# SCH_HackerCard.net
KiCad netlist of a schematic drawn in EasyEDA
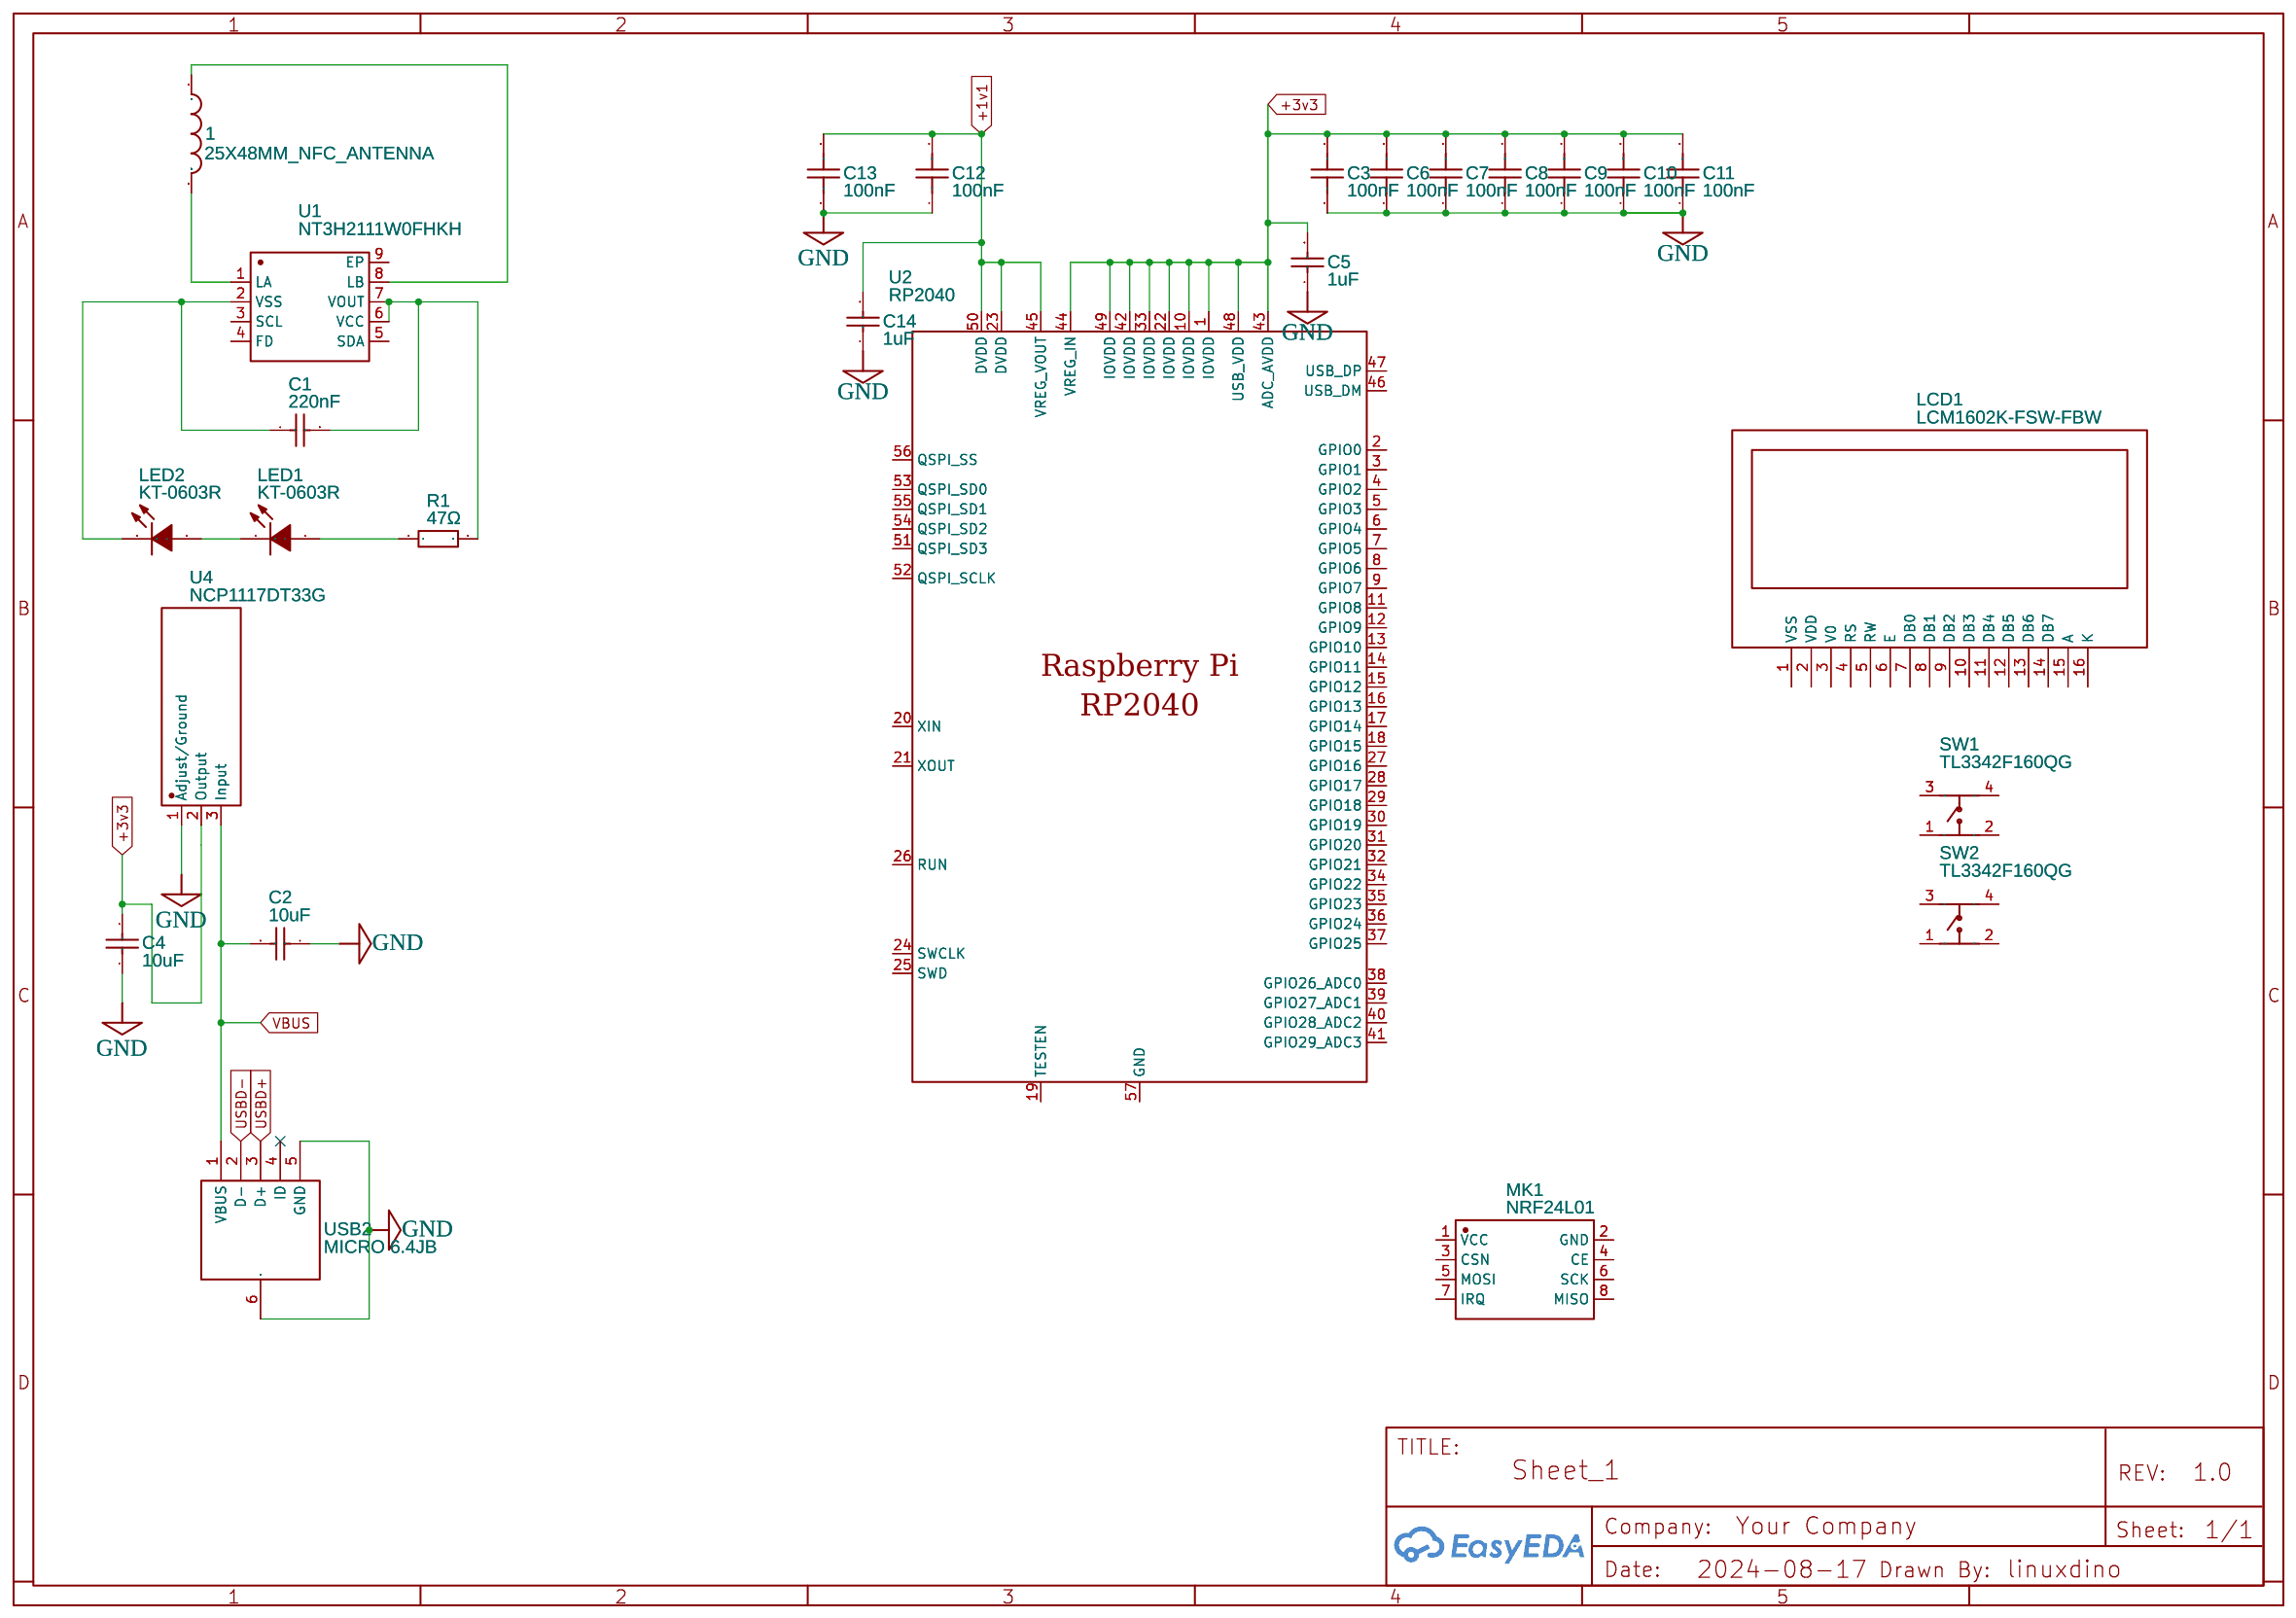
[diagram p0: schematic sheet]

(export (version "E")
  (design (tool "Eeschema 10.0.6"))
  (components
    (comp (ref "1") (value "25X48MM_NFC_ANTENNA") (libsource (lib "") (part "25X48MM_NFC_ANTENNA")))
    (comp (ref "C1")
      (value "220nF")
      (fields
        (field (name "Manufacturer Part") "CL10B224KA8NNNC")
        (field (name "Manufacturer") "SAMSUNG(三星)")
      )
      (libsource (lib "") (part "CL10B224KA8NNNC"))
    )
    (comp (ref "C2")
      (value "10uF")
      (fields
        (field (name "Manufacturer Part") "CL31A106KOHNNNE")
        (field (name "Manufacturer") "SAMSUNG(三星)")
      )
      (libsource (lib "") (part "CL31A106KOHNNNE"))
    )
    (comp (ref "C3")
      (value "100nF")
      (fields
        (field (name "Manufacturer Part") "CL10B104KB8NNNC")
        (field (name "Manufacturer") "SAMSUNG(三星)")
      )
      (libsource (lib "") (part "CL10B104KB8NNNC"))
    )
    (comp (ref "C4")
      (value "10uF")
      (fields
        (field (name "Manufacturer Part") "CL31A106KOHNNNE")
        (field (name "Manufacturer") "SAMSUNG(三星)")
      )
      (libsource (lib "") (part "CL31A106KOHNNNE_1"))
    )
    (comp (ref "C5")
      (value "1uF")
      (fields
        (field (name "Manufacturer Part") "CL10A105KO8NNNC")
        (field (name "Manufacturer") "SAMSUNG(三星)")
      )
      (libsource (lib "") (part "CL10A105KO8NNNC"))
    )
    (comp (ref "C6")
      (value "100nF")
      (fields
        (field (name "Manufacturer Part") "CL10B104KB8NNNC")
        (field (name "Manufacturer") "SAMSUNG(三星)")
      )
      (libsource (lib "") (part "CL10B104KB8NNNC"))
    )
    (comp (ref "C7")
      (value "100nF")
      (fields
        (field (name "Manufacturer Part") "CL10B104KB8NNNC")
        (field (name "Manufacturer") "SAMSUNG(三星)")
      )
      (libsource (lib "") (part "CL10B104KB8NNNC"))
    )
    (comp (ref "C8")
      (value "100nF")
      (fields
        (field (name "Manufacturer Part") "CL10B104KB8NNNC")
        (field (name "Manufacturer") "SAMSUNG(三星)")
      )
      (libsource (lib "") (part "CL10B104KB8NNNC"))
    )
    (comp (ref "C9")
      (value "100nF")
      (fields
        (field (name "Manufacturer Part") "CL10B104KB8NNNC")
        (field (name "Manufacturer") "SAMSUNG(三星)")
      )
      (libsource (lib "") (part "CL10B104KB8NNNC"))
    )
    (comp (ref "C10")
      (value "100nF")
      (fields
        (field (name "Manufacturer Part") "CL10B104KB8NNNC")
        (field (name "Manufacturer") "SAMSUNG(三星)")
      )
      (libsource (lib "") (part "CL10B104KB8NNNC"))
    )
    (comp (ref "C11")
      (value "100nF")
      (fields
        (field (name "Manufacturer Part") "CL10B104KB8NNNC")
        (field (name "Manufacturer") "SAMSUNG(三星)")
      )
      (libsource (lib "") (part "CL10B104KB8NNNC"))
    )
    (comp (ref "C12")
      (value "100nF")
      (fields
        (field (name "Manufacturer Part") "CL10B104KB8NNNC")
        (field (name "Manufacturer") "SAMSUNG(三星)")
      )
      (libsource (lib "") (part "CL10B104KB8NNNC"))
    )
    (comp (ref "C13")
      (value "100nF")
      (fields
        (field (name "Manufacturer Part") "CL10B104KB8NNNC")
        (field (name "Manufacturer") "SAMSUNG(三星)")
      )
      (libsource (lib "") (part "CL10B104KB8NNNC"))
    )
    (comp (ref "C14")
      (value "1uF")
      (fields
        (field (name "Manufacturer Part") "CL10A105KO8NNNC")
        (field (name "Manufacturer") "SAMSUNG(三星)")
      )
      (libsource (lib "") (part "CL10A105KO8NNNC"))
    )
    (comp (ref "LCD1")
      (value "LCM1602K-FSW-FBW")
      (fields (field (name "Manufacturer") "LONTECH(厦门龙特)"))
      (libsource (lib "") (part "LCM1602K-FSW-FBW"))
    )
    (comp (ref "LED1")
      (value "KT-0603R")
      (fields (field (name "Manufacturer") "KENTO"))
      (libsource (lib "") (part "KT-0603R"))
    )
    (comp (ref "LED2")
      (value "KT-0603R")
      (fields (field (name "Manufacturer") "KENTO"))
      (libsource (lib "") (part "KT-0603R"))
    )
    (comp (ref "MK1")
      (value "NRF24L01")
      (fields (field (name "Manufacturer Part") "NF-04") (field (name "Manufacturer") "Ai-Thinker(安信可)"))
      (libsource (lib "") (part "NRF24L01"))
    )
    (comp (ref "R1")
      (value "47Ω")
      (fields
        (field (name "Manufacturer Part") "0603WAF470JT5E")
        (field (name "Manufacturer") "UNI-ROYAL(厚声)")
      )
      (libsource (lib "") (part "0603WAF470JT5E"))
    )
    (comp (ref "SW1")
      (value "TL3342F160QG")
      (fields (field (name "Manufacturer") "E-Switch"))
      (libsource (lib "") (part "TL3342F160QG"))
    )
    (comp (ref "SW2")
      (value "TL3342F160QG")
      (fields (field (name "Manufacturer") "E-Switch"))
      (libsource (lib "") (part "TL3342F160QG"))
    )
    (comp (ref "U1")
      (value "NT3H2111W0FHKH")
      (fields (field (name "Manufacturer") "NXP(恩智浦)"))
      (libsource (lib "") (part "NT3H2111W0FHKH"))
    )
    (comp (ref "U2")
      (value "RP2040")
      (fields (field (name "Manufacturer") "Raspberry Pi(树莓派)"))
      (libsource (lib "") (part "RP2040"))
    )
    (comp (ref "U4")
      (value "NCP1117DT33G")
      (fields (field (name "Manufacturer") "onsemi(安森美)"))
      (libsource (lib "") (part "NCP1117DT33G"))
    )
    (comp (ref "USB2")
      (value "MICRO 6.4JB")
      (fields (field (name "Manufacturer") "SHOU HAN(首韩)"))
      (libsource (lib "") (part "MICRO 6.4JB"))
    )
  )
  (nets
    (net (code "1") (name "+1v1") (class "Default")
      (node (ref "C12") (pin "2") (pinfunction "2_2") (pintype "unspecified"))
      (node (ref "C13") (pin "2") (pinfunction "2_2") (pintype "unspecified"))
      (node (ref "C14") (pin "2") (pinfunction "2_2") (pintype "input"))
      (node (ref "U2") (pin "23") (pinfunction "DVDD_23") (pintype "bidirectional"))
      (node (ref "U2") (pin "45") (pinfunction "VREG_VOUT_45") (pintype "bidirectional"))
      (node (ref "U2") (pin "50") (pinfunction "DVDD_50") (pintype "bidirectional"))
    )
    (net (code "2") (name "+3v3") (class "Default")
      (node (ref "C10") (pin "2") (pinfunction "2_2") (pintype "unspecified"))
      (node (ref "C11") (pin "2") (pinfunction "2_2") (pintype "unspecified"))
      (node (ref "C3") (pin "2") (pinfunction "2_2") (pintype "unspecified"))
      (node (ref "C4") (pin "2") (pinfunction "2_2") (pintype "input"))
      (node (ref "C5") (pin "2") (pinfunction "2_2") (pintype "input"))
      (node (ref "C6") (pin "2") (pinfunction "2_2") (pintype "unspecified"))
      (node (ref "C7") (pin "2") (pinfunction "2_2") (pintype "unspecified"))
      (node (ref "C8") (pin "2") (pinfunction "2_2") (pintype "unspecified"))
      (node (ref "C9") (pin "2") (pinfunction "2_2") (pintype "unspecified"))
      (node (ref "U2") (pin "1") (pinfunction "IOVDD_1") (pintype "bidirectional"))
      (node (ref "U2") (pin "10") (pinfunction "IOVDD_10") (pintype "bidirectional"))
      (node (ref "U2") (pin "22") (pinfunction "IOVDD_22") (pintype "bidirectional"))
      (node (ref "U2") (pin "33") (pinfunction "IOVDD_33") (pintype "bidirectional"))
      (node (ref "U2") (pin "42") (pinfunction "IOVDD_42") (pintype "bidirectional"))
      (node (ref "U2") (pin "43") (pinfunction "ADC_AVDD_43") (pintype "bidirectional"))
      (node (ref "U2") (pin "44") (pinfunction "VREG_IN_44") (pintype "bidirectional"))
      (node (ref "U2") (pin "48") (pinfunction "USB_VDD_48") (pintype "bidirectional"))
      (node (ref "U2") (pin "49") (pinfunction "IOVDD_49") (pintype "bidirectional"))
      (node (ref "U4") (pin "2") (pinfunction "Output_2") (pintype "unspecified"))
    )
    (net (code "3") (name "GND") (class "Default")
      (node (ref "C10") (pin "1") (pinfunction "1_1") (pintype "unspecified"))
      (node (ref "C11") (pin "1") (pinfunction "1_1") (pintype "unspecified"))
      (node (ref "C12") (pin "1") (pinfunction "1_1") (pintype "unspecified"))
      (node (ref "C13") (pin "1") (pinfunction "1_1") (pintype "unspecified"))
      (node (ref "C14") (pin "1") (pinfunction "1_1") (pintype "input"))
      (node (ref "C2") (pin "1") (pinfunction "1_1") (pintype "input"))
      (node (ref "C3") (pin "1") (pinfunction "1_1") (pintype "unspecified"))
      (node (ref "C4") (pin "1") (pinfunction "1_1") (pintype "input"))
      (node (ref "C5") (pin "1") (pinfunction "1_1") (pintype "input"))
      (node (ref "C6") (pin "1") (pinfunction "1_1") (pintype "unspecified"))
      (node (ref "C7") (pin "1") (pinfunction "1_1") (pintype "unspecified"))
      (node (ref "C8") (pin "1") (pinfunction "1_1") (pintype "unspecified"))
      (node (ref "C9") (pin "1") (pinfunction "1_1") (pintype "unspecified"))
      (node (ref "U4") (pin "1") (pinfunction "Adjust/Ground_1") (pintype "unspecified"))
      (node (ref "USB2") (pin "5") (pinfunction "GND_5") (pintype "input"))
      (node (ref "USB2") (pin "6") (pinfunction "EH_6") (pintype "input"))
    )
    (net (code "4") (name "Net-(LED1-A)") (class "Default")
      (node (ref "LED1") (pin "2") (pinfunction "A_2") (pintype "unspecified"))
      (node (ref "R1") (pin "1") (pinfunction "1_1") (pintype "input"))
    )
    (net (code "5") (name "Net-(LED1-K)") (class "Default")
      (node (ref "LED1") (pin "1") (pinfunction "K_1") (pintype "unspecified"))
      (node (ref "LED2") (pin "2") (pinfunction "A_2") (pintype "unspecified"))
    )
    (net (code "6") (name "Net-(LED2-K)") (class "Default")
      (node (ref "C1") (pin "1") (pinfunction "1_1") (pintype "input"))
      (node (ref "LED2") (pin "1") (pinfunction "K_1") (pintype "unspecified"))
      (node (ref "U1") (pin "2") (pinfunction "VSS_2") (pintype "unspecified"))
    )
    (net (code "7") (name "Net-(U1-LA)") (class "Default")
      (node (ref "1") (pin "P$2") (pinfunction "P$2_P$2") (pintype "bidirectional"))
      (node (ref "U1") (pin "1") (pinfunction "LA_1") (pintype "unspecified"))
    )
    (net (code "8") (name "Net-(U1-LB)") (class "Default")
      (node (ref "1") (pin "P$1") (pinfunction "P$1_P$1") (pintype "bidirectional"))
      (node (ref "U1") (pin "8") (pinfunction "LB_8") (pintype "unspecified"))
    )
    (net (code "9") (name "Net-(U1-VCC)") (class "Default")
      (node (ref "C1") (pin "2") (pinfunction "2_2") (pintype "input"))
      (node (ref "R1") (pin "2") (pinfunction "2_2") (pintype "input"))
      (node (ref "U1") (pin "6") (pinfunction "VCC_6") (pintype "unspecified"))
      (node (ref "U1") (pin "7") (pinfunction "VOUT_7") (pintype "unspecified"))
    )
    (net (code "10") (name "USBD+") (class "Default")
      (node (ref "USB2") (pin "3") (pinfunction "D+_3") (pintype "input"))
    )
    (net (code "11") (name "USBD-") (class "Default")
      (node (ref "USB2") (pin "2") (pinfunction "D-_2") (pintype "input"))
    )
    (net (code "12") (name "VBUS") (class "Default")
      (node (ref "C2") (pin "2") (pinfunction "2_2") (pintype "input"))
      (node (ref "U4") (pin "3") (pinfunction "Input_3") (pintype "unspecified"))
      (node (ref "USB2") (pin "1") (pinfunction "VBUS_1") (pintype "input"))
    )
    (net (code "13") (name "unconnected-(LCD1-A-Pad15)") (class "Default")
      (node (ref "LCD1") (pin "15") (pinfunction "A_15") (pintype "unspecified"))
    )
    (net (code "14") (name "unconnected-(LCD1-DB0-Pad7)") (class "Default")
      (node (ref "LCD1") (pin "7") (pinfunction "DB0_7") (pintype "unspecified"))
    )
    (net (code "15") (name "unconnected-(LCD1-DB1-Pad8)") (class "Default")
      (node (ref "LCD1") (pin "8") (pinfunction "DB1_8") (pintype "unspecified"))
    )
    (net (code "16") (name "unconnected-(LCD1-DB2-Pad9)") (class "Default")
      (node (ref "LCD1") (pin "9") (pinfunction "DB2_9") (pintype "unspecified"))
    )
    (net (code "17") (name "unconnected-(LCD1-DB3-Pad10)") (class "Default")
      (node (ref "LCD1") (pin "10") (pinfunction "DB3_10") (pintype "unspecified"))
    )
    (net (code "18") (name "unconnected-(LCD1-DB4-Pad11)") (class "Default")
      (node (ref "LCD1") (pin "11") (pinfunction "DB4_11") (pintype "unspecified"))
    )
    (net (code "19") (name "unconnected-(LCD1-DB5-Pad12)") (class "Default")
      (node (ref "LCD1") (pin "12") (pinfunction "DB5_12") (pintype "unspecified"))
    )
    (net (code "20") (name "unconnected-(LCD1-DB6-Pad13)") (class "Default")
      (node (ref "LCD1") (pin "13") (pinfunction "DB6_13") (pintype "unspecified"))
    )
    (net (code "21") (name "unconnected-(LCD1-DB7-Pad14)") (class "Default")
      (node (ref "LCD1") (pin "14") (pinfunction "DB7_14") (pintype "unspecified"))
    )
    (net (code "22") (name "unconnected-(LCD1-E-Pad6)") (class "Default")
      (node (ref "LCD1") (pin "6") (pinfunction "E_6") (pintype "unspecified"))
    )
    (net (code "23") (name "unconnected-(LCD1-K-Pad16)") (class "Default")
      (node (ref "LCD1") (pin "16") (pinfunction "K_16") (pintype "unspecified"))
    )
    (net (code "24") (name "unconnected-(LCD1-RS-Pad4)") (class "Default")
      (node (ref "LCD1") (pin "4") (pinfunction "RS_4") (pintype "unspecified"))
    )
    (net (code "25") (name "unconnected-(LCD1-RW-Pad5)") (class "Default")
      (node (ref "LCD1") (pin "5") (pinfunction "RW_5") (pintype "unspecified"))
    )
    (net (code "26") (name "unconnected-(LCD1-V0-Pad3)") (class "Default")
      (node (ref "LCD1") (pin "3") (pinfunction "V0_3") (pintype "unspecified"))
    )
    (net (code "27") (name "unconnected-(LCD1-VDD-Pad2)") (class "Default")
      (node (ref "LCD1") (pin "2") (pinfunction "VDD_2") (pintype "unspecified"))
    )
    (net (code "28") (name "unconnected-(LCD1-VSS-Pad1)") (class "Default")
      (node (ref "LCD1") (pin "1") (pinfunction "VSS_1") (pintype "unspecified"))
    )
    (net (code "29") (name "unconnected-(MK1-CE-Pad4)") (class "Default")
      (node (ref "MK1") (pin "4") (pinfunction "CE_4") (pintype "unspecified"))
    )
    (net (code "30") (name "unconnected-(MK1-CSN-Pad3)") (class "Default")
      (node (ref "MK1") (pin "3") (pinfunction "CSN_3") (pintype "unspecified"))
    )
    (net (code "31") (name "unconnected-(MK1-GND-Pad2)") (class "Default")
      (node (ref "MK1") (pin "2") (pinfunction "GND_2") (pintype "unspecified"))
    )
    (net (code "32") (name "unconnected-(MK1-IRQ-Pad7)") (class "Default")
      (node (ref "MK1") (pin "7") (pinfunction "IRQ_7") (pintype "unspecified"))
    )
    (net (code "33") (name "unconnected-(MK1-MISO-Pad8)") (class "Default")
      (node (ref "MK1") (pin "8") (pinfunction "MISO_8") (pintype "unspecified"))
    )
    (net (code "34") (name "unconnected-(MK1-MOSI-Pad5)") (class "Default")
      (node (ref "MK1") (pin "5") (pinfunction "MOSI_5") (pintype "unspecified"))
    )
    (net (code "35") (name "unconnected-(MK1-SCK-Pad6)") (class "Default")
      (node (ref "MK1") (pin "6") (pinfunction "SCK_6") (pintype "unspecified"))
    )
    (net (code "36") (name "unconnected-(MK1-VCC-Pad1)") (class "Default")
      (node (ref "MK1") (pin "1") (pinfunction "VCC_1") (pintype "unspecified"))
    )
    (net (code "37") (name "unconnected-(SW1-Pad1)") (class "Default")
      (node (ref "SW1") (pin "1") (pinfunction "1_1") (pintype "unspecified"))
    )
    (net (code "38") (name "unconnected-(SW1-Pad2)") (class "Default")
      (node (ref "SW1") (pin "2") (pinfunction "2_2") (pintype "unspecified"))
    )
    (net (code "39") (name "unconnected-(SW1-Pad3)") (class "Default")
      (node (ref "SW1") (pin "3") (pinfunction "3_3") (pintype "unspecified"))
    )
    (net (code "40") (name "unconnected-(SW1-Pad4)") (class "Default")
      (node (ref "SW1") (pin "4") (pinfunction "4_4") (pintype "unspecified"))
    )
    (net (code "41") (name "unconnected-(SW2-Pad1)") (class "Default")
      (node (ref "SW2") (pin "1") (pinfunction "1_1") (pintype "unspecified"))
    )
    (net (code "42") (name "unconnected-(SW2-Pad2)") (class "Default")
      (node (ref "SW2") (pin "2") (pinfunction "2_2") (pintype "unspecified"))
    )
    (net (code "43") (name "unconnected-(SW2-Pad3)") (class "Default")
      (node (ref "SW2") (pin "3") (pinfunction "3_3") (pintype "unspecified"))
    )
    (net (code "44") (name "unconnected-(SW2-Pad4)") (class "Default")
      (node (ref "SW2") (pin "4") (pinfunction "4_4") (pintype "unspecified"))
    )
    (net (code "45") (name "unconnected-(U1-EP-Pad9)") (class "Default")
      (node (ref "U1") (pin "9") (pinfunction "EP_9") (pintype "unspecified"))
    )
    (net (code "46") (name "unconnected-(U1-FD-Pad4)") (class "Default")
      (node (ref "U1") (pin "4") (pinfunction "FD_4") (pintype "unspecified"))
    )
    (net (code "47") (name "unconnected-(U1-SCL-Pad3)") (class "Default")
      (node (ref "U1") (pin "3") (pinfunction "SCL_3") (pintype "unspecified"))
    )
    (net (code "48") (name "unconnected-(U1-SDA-Pad5)") (class "Default")
      (node (ref "U1") (pin "5") (pinfunction "SDA_5") (pintype "unspecified"))
    )
    (net (code "49") (name "unconnected-(U2-GND-Pad57)") (class "Default")
      (node (ref "U2") (pin "57") (pinfunction "GND_57") (pintype "bidirectional"))
    )
    (net (code "50") (name "unconnected-(U2-GPIO0-Pad2)") (class "Default")
      (node (ref "U2") (pin "2") (pinfunction "GPIO0_2") (pintype "bidirectional"))
    )
    (net (code "51") (name "unconnected-(U2-GPIO1-Pad3)") (class "Default")
      (node (ref "U2") (pin "3") (pinfunction "GPIO1_3") (pintype "bidirectional"))
    )
    (net (code "52") (name "unconnected-(U2-GPIO2-Pad4)") (class "Default")
      (node (ref "U2") (pin "4") (pinfunction "GPIO2_4") (pintype "bidirectional"))
    )
    (net (code "53") (name "unconnected-(U2-GPIO3-Pad5)") (class "Default")
      (node (ref "U2") (pin "5") (pinfunction "GPIO3_5") (pintype "bidirectional"))
    )
    (net (code "54") (name "unconnected-(U2-GPIO4-Pad6)") (class "Default")
      (node (ref "U2") (pin "6") (pinfunction "GPIO4_6") (pintype "bidirectional"))
    )
    (net (code "55") (name "unconnected-(U2-GPIO5-Pad7)") (class "Default")
      (node (ref "U2") (pin "7") (pinfunction "GPIO5_7") (pintype "bidirectional"))
    )
    (net (code "56") (name "unconnected-(U2-GPIO6-Pad8)") (class "Default")
      (node (ref "U2") (pin "8") (pinfunction "GPIO6_8") (pintype "bidirectional"))
    )
    (net (code "57") (name "unconnected-(U2-GPIO7-Pad9)") (class "Default")
      (node (ref "U2") (pin "9") (pinfunction "GPIO7_9") (pintype "bidirectional"))
    )
    (net (code "58") (name "unconnected-(U2-GPIO8-Pad11)") (class "Default")
      (node (ref "U2") (pin "11") (pinfunction "GPIO8_11") (pintype "bidirectional"))
    )
    (net (code "59") (name "unconnected-(U2-GPIO9-Pad12)") (class "Default")
      (node (ref "U2") (pin "12") (pinfunction "GPIO9_12") (pintype "bidirectional"))
    )
    (net (code "60") (name "unconnected-(U2-GPIO10-Pad13)") (class "Default")
      (node (ref "U2") (pin "13") (pinfunction "GPIO10_13") (pintype "bidirectional"))
    )
    (net (code "61") (name "unconnected-(U2-GPIO11-Pad14)") (class "Default")
      (node (ref "U2") (pin "14") (pinfunction "GPIO11_14") (pintype "bidirectional"))
    )
    (net (code "62") (name "unconnected-(U2-GPIO12-Pad15)") (class "Default")
      (node (ref "U2") (pin "15") (pinfunction "GPIO12_15") (pintype "bidirectional"))
    )
    (net (code "63") (name "unconnected-(U2-GPIO13-Pad16)") (class "Default")
      (node (ref "U2") (pin "16") (pinfunction "GPIO13_16") (pintype "bidirectional"))
    )
    (net (code "64") (name "unconnected-(U2-GPIO14-Pad17)") (class "Default")
      (node (ref "U2") (pin "17") (pinfunction "GPIO14_17") (pintype "bidirectional"))
    )
    (net (code "65") (name "unconnected-(U2-GPIO15-Pad18)") (class "Default")
      (node (ref "U2") (pin "18") (pinfunction "GPIO15_18") (pintype "bidirectional"))
    )
    (net (code "66") (name "unconnected-(U2-GPIO16-Pad27)") (class "Default")
      (node (ref "U2") (pin "27") (pinfunction "GPIO16_27") (pintype "bidirectional"))
    )
    (net (code "67") (name "unconnected-(U2-GPIO17-Pad28)") (class "Default")
      (node (ref "U2") (pin "28") (pinfunction "GPIO17_28") (pintype "bidirectional"))
    )
    (net (code "68") (name "unconnected-(U2-GPIO18-Pad29)") (class "Default")
      (node (ref "U2") (pin "29") (pinfunction "GPIO18_29") (pintype "bidirectional"))
    )
    (net (code "69") (name "unconnected-(U2-GPIO19-Pad30)") (class "Default")
      (node (ref "U2") (pin "30") (pinfunction "GPIO19_30") (pintype "bidirectional"))
    )
    (net (code "70") (name "unconnected-(U2-GPIO20-Pad31)") (class "Default")
      (node (ref "U2") (pin "31") (pinfunction "GPIO20_31") (pintype "bidirectional"))
    )
    (net (code "71") (name "unconnected-(U2-GPIO21-Pad32)") (class "Default")
      (node (ref "U2") (pin "32") (pinfunction "GPIO21_32") (pintype "bidirectional"))
    )
    (net (code "72") (name "unconnected-(U2-GPIO22-Pad34)") (class "Default")
      (node (ref "U2") (pin "34") (pinfunction "GPIO22_34") (pintype "bidirectional"))
    )
    (net (code "73") (name "unconnected-(U2-GPIO23-Pad35)") (class "Default")
      (node (ref "U2") (pin "35") (pinfunction "GPIO23_35") (pintype "bidirectional"))
    )
    (net (code "74") (name "unconnected-(U2-GPIO24-Pad36)") (class "Default")
      (node (ref "U2") (pin "36") (pinfunction "GPIO24_36") (pintype "bidirectional"))
    )
    (net (code "75") (name "unconnected-(U2-GPIO25-Pad37)") (class "Default")
      (node (ref "U2") (pin "37") (pinfunction "GPIO25_37") (pintype "bidirectional"))
    )
    (net (code "76") (name "unconnected-(U2-GPIO26_ADC0-Pad38)") (class "Default")
      (node (ref "U2") (pin "38") (pinfunction "GPIO26_ADC0_38") (pintype "bidirectional"))
    )
    (net (code "77") (name "unconnected-(U2-GPIO27_ADC1-Pad39)") (class "Default")
      (node (ref "U2") (pin "39") (pinfunction "GPIO27_ADC1_39") (pintype "bidirectional"))
    )
    (net (code "78") (name "unconnected-(U2-GPIO28_ADC2-Pad40)") (class "Default")
      (node (ref "U2") (pin "40") (pinfunction "GPIO28_ADC2_40") (pintype "bidirectional"))
    )
    (net (code "79") (name "unconnected-(U2-GPIO29_ADC3-Pad41)") (class "Default")
      (node (ref "U2") (pin "41") (pinfunction "GPIO29_ADC3_41") (pintype "bidirectional"))
    )
    (net (code "80") (name "unconnected-(U2-QSPI_SCLK-Pad52)") (class "Default")
      (node (ref "U2") (pin "52") (pinfunction "QSPI_SCLK_52") (pintype "output"))
    )
    (net (code "81") (name "unconnected-(U2-QSPI_SD0-Pad53)") (class "Default")
      (node (ref "U2") (pin "53") (pinfunction "QSPI_SD0_53") (pintype "bidirectional"))
    )
    (net (code "82") (name "unconnected-(U2-QSPI_SD1-Pad55)") (class "Default")
      (node (ref "U2") (pin "55") (pinfunction "QSPI_SD1_55") (pintype "bidirectional"))
    )
    (net (code "83") (name "unconnected-(U2-QSPI_SD2-Pad54)") (class "Default")
      (node (ref "U2") (pin "54") (pinfunction "QSPI_SD2_54") (pintype "bidirectional"))
    )
    (net (code "84") (name "unconnected-(U2-QSPI_SD3-Pad51)") (class "Default")
      (node (ref "U2") (pin "51") (pinfunction "QSPI_SD3_51") (pintype "bidirectional"))
    )
    (net (code "85") (name "unconnected-(U2-QSPI_SS-Pad56)") (class "Default")
      (node (ref "U2") (pin "56") (pinfunction "QSPI_SS_56") (pintype "bidirectional"))
    )
    (net (code "86") (name "unconnected-(U2-RUN-Pad26)") (class "Default")
      (node (ref "U2") (pin "26") (pinfunction "RUN_26") (pintype "input"))
    )
    (net (code "87") (name "unconnected-(U2-SWCLK-Pad24)") (class "Default")
      (node (ref "U2") (pin "24") (pinfunction "SWCLK_24") (pintype "output"))
    )
    (net (code "88") (name "unconnected-(U2-SWD-Pad25)") (class "Default")
      (node (ref "U2") (pin "25") (pinfunction "SWD_25") (pintype "bidirectional"))
    )
    (net (code "89") (name "unconnected-(U2-TESTEN-Pad19)") (class "Default")
      (node (ref "U2") (pin "19") (pinfunction "TESTEN_19") (pintype "unspecified"))
    )
    (net (code "90") (name "unconnected-(U2-USB_DM-Pad46)") (class "Default")
      (node (ref "U2") (pin "46") (pinfunction "USB_DM_46") (pintype "bidirectional"))
    )
    (net (code "91") (name "unconnected-(U2-USB_DP-Pad47)") (class "Default")
      (node (ref "U2") (pin "47") (pinfunction "USB_DP_47") (pintype "bidirectional"))
    )
    (net (code "92") (name "unconnected-(U2-XIN-Pad20)") (class "Default")
      (node (ref "U2") (pin "20") (pinfunction "XIN_20") (pintype "input"))
    )
    (net (code "93") (name "unconnected-(U2-XOUT-Pad21)") (class "Default")
      (node (ref "U2") (pin "21") (pinfunction "XOUT_21") (pintype "unspecified"))
    )
    (net (code "94") (name "unconnected-(USB2-ID-Pad4)") (class "Default")
      (node (ref "USB2") (pin "4") (pinfunction "ID_4") (pintype "input+no_connect"))
    )
  )
)
